# one_dollar_boad.net
KiCad netlist of a schematic drawn in EAGLE
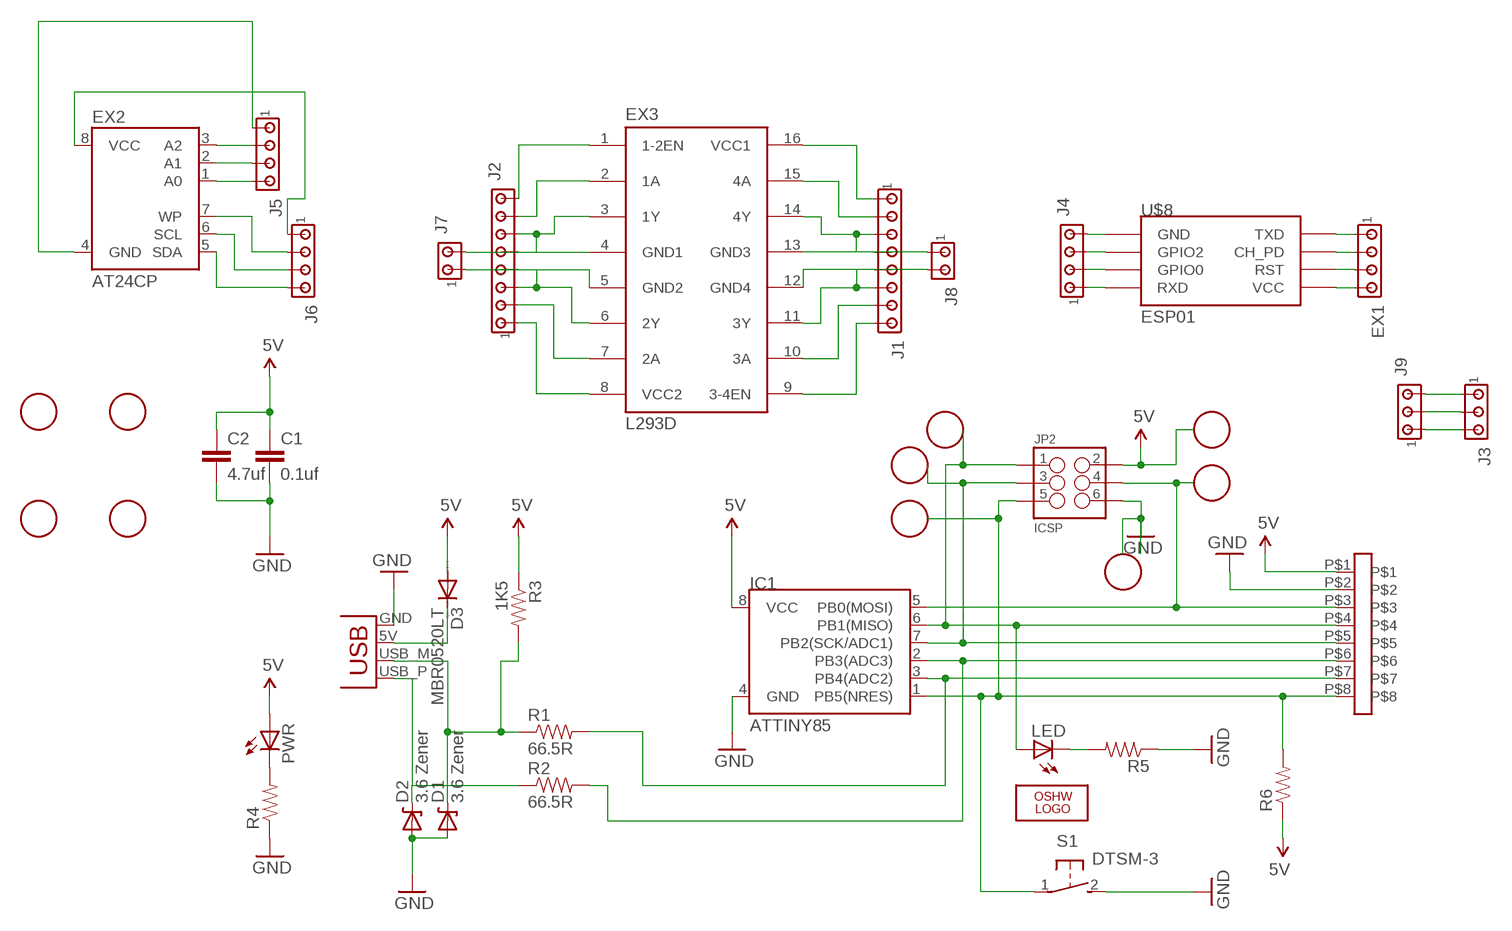
[diagram p0: schematic, sheet 1]

(export (version "E")
  (design (tool "Eeschema 10.0.6"))
  (components
    (comp (ref "C1")
      (value "0.1uf")
      (footprint "eagle-import:0402-CAP")
      (libsource (lib "eagle-import") (part "CAP0402-CAP"))
    )
    (comp (ref "C2")
      (value "4.7uf")
      (footprint "eagle-import:0805")
      (libsource (lib "eagle-import") (part "CAP0805"))
    )
    (comp (ref "CONNECTORBAR1")
      (value "FAMALEBAR01X08")
      (footprint "eagle-import:FEMEABARRA01X08")
      (libsource (lib "eagle-import") (part "FAMALEBAR01X08"))
    )
    (comp (ref "D1")
      (value "3.6 Zener")
      (footprint "eagle-import:SOD-323")
      (libsource (lib "eagle-import") (part "DIODE-ZENER-BZT52"))
    )
    (comp (ref "D2")
      (value "3.6 Zener")
      (footprint "eagle-import:SOD-323")
      (libsource (lib "eagle-import") (part "DIODE-ZENER-BZT52"))
    )
    (comp (ref "D3")
      (value "MBR0520LT")
      (footprint "eagle-import:SOD123")
      (libsource (lib "eagle-import") (part "MBR0520LT"))
    )
    (comp (ref "EX1")
      (value "MTA04-100")
      (footprint "eagle-import:10X04MTA")
      (libsource (lib "eagle-import") (part "MTA04-100"))
    )
    (comp (ref "EX2")
      (value "AT24CP")
      (footprint "eagle-import:DIL08")
      (fields (field (name "MPN") "AT24C1024BW-SH-B"))
      (libsource (lib "eagle-import") (part "AT24CP"))
    )
    (comp (ref "EX3")
      (value "L293D")
      (footprint "eagle-import:DIL16")
      (libsource (lib "eagle-import") (part "L293D"))
    )
    (comp (ref "IC1")
      (value "ATTINY85")
      (footprint "eagle-import:SO08-EIAJ")
      (libsource (lib "eagle-import") (part "ATTINY45"))
    )
    (comp (ref "ICSP1")
      (value "ICSP")
      (footprint "eagle-import:ICSP")
      (libsource (lib "eagle-import") (part "ICSP"))
    )
    (comp (ref "ICSP2")
      (value "ICSP")
      (footprint "eagle-import:ICSP")
      (libsource (lib "eagle-import") (part "ICSP"))
    )
    (comp (ref "ICSP3")
      (value "ICSP")
      (footprint "eagle-import:ICSP")
      (libsource (lib "eagle-import") (part "ICSP"))
    )
    (comp (ref "ICSP4")
      (value "ICSP")
      (footprint "eagle-import:ICSP")
      (libsource (lib "eagle-import") (part "ICSP"))
    )
    (comp (ref "ICSP5")
      (value "ICSP")
      (footprint "eagle-import:ICSP")
      (libsource (lib "eagle-import") (part "ICSP"))
    )
    (comp (ref "ICSP6")
      (value "ICSP")
      (footprint "eagle-import:ICSP")
      (libsource (lib "eagle-import") (part "ICSP"))
    )
    (comp (ref "J1")
      (value "MTA08-100")
      (footprint "eagle-import:10X08MTA")
      (libsource (lib "eagle-import") (part "MTA08-100"))
    )
    (comp (ref "J2")
      (value "MTA08-100")
      (footprint "eagle-import:10X08MTA")
      (libsource (lib "eagle-import") (part "MTA08-100"))
    )
    (comp (ref "J3")
      (value "MTA03-100")
      (footprint "eagle-import:10X03MTA")
      (libsource (lib "eagle-import") (part "MTA03-100"))
    )
    (comp (ref "J4")
      (value "MTA04-100")
      (footprint "eagle-import:10X04MTA")
      (libsource (lib "eagle-import") (part "MTA04-100"))
    )
    (comp (ref "J5")
      (value "MTA04-100")
      (footprint "eagle-import:10X04MTA")
      (libsource (lib "eagle-import") (part "MTA04-100"))
    )
    (comp (ref "J6")
      (value "MTA04-100")
      (footprint "eagle-import:10X04MTA")
      (libsource (lib "eagle-import") (part "MTA04-100"))
    )
    (comp (ref "J7")
      (value "MTA02-100")
      (footprint "eagle-import:10X02MTA")
      (libsource (lib "eagle-import") (part "MTA02-100"))
    )
    (comp (ref "J8")
      (value "MTA02-100")
      (footprint "eagle-import:10X02MTA")
      (libsource (lib "eagle-import") (part "MTA02-100"))
    )
    (comp (ref "J9")
      (value "MTA03-100")
      (footprint "eagle-import:10X03MTA")
      (libsource (lib "eagle-import") (part "MTA03-100"))
    )
    (comp (ref "JP2")
      (value "ICSP")
      (footprint "eagle-import:2X3")
      (libsource (lib "eagle-import") (part "M03X22X3_SILK_MALE_PTH"))
    )
    (comp (ref "LED")
      (value "LED0603")
      (footprint "eagle-import:LED-0603")
      (libsource (lib "eagle-import") (part "LED0603"))
    )
    (comp (ref "LOGO2")
      (value "LOGO-OSHW-10MILX0200-NT")
      (footprint "eagle-import:OSHW_10X200_NOTEXT")
      (libsource (lib "eagle-import") (part "LOGO-OSHW-10MILX0200-NT"))
    )
    (comp (ref "PWR")
      (value "LED0603")
      (footprint "eagle-import:LED-0603")
      (libsource (lib "eagle-import") (part "LED0603"))
    )
    (comp (ref "R1")
      (value "66.5R")
      (footprint "eagle-import:0402-RES")
      (libsource (lib "eagle-import") (part "RESISTOR0402-RES"))
    )
    (comp (ref "R2")
      (value "66.5R")
      (footprint "eagle-import:0402-RES")
      (libsource (lib "eagle-import") (part "RESISTOR0402-RES"))
    )
    (comp (ref "R3")
      (value "1K5")
      (footprint "eagle-import:0402-RES")
      (libsource (lib "eagle-import") (part "RESISTOR0402-RES"))
    )
    (comp (ref "R4")
      (value "RESISTOR0402-RES")
      (footprint "eagle-import:0402-RES")
      (libsource (lib "eagle-import") (part "RESISTOR0402-RES"))
    )
    (comp (ref "R5")
      (value "RESISTOR0402-RES")
      (footprint "eagle-import:0402-RES")
      (libsource (lib "eagle-import") (part "RESISTOR0402-RES"))
    )
    (comp (ref "R6")
      (value "RESISTOR0402-RES")
      (footprint "eagle-import:0402-RES")
      (libsource (lib "eagle-import") (part "SparkFun-Passives_RESISTOR0402-RES"))
    )
    (comp (ref "S1")
      (value "DTSM-3")
      (footprint "eagle-import:DTSM-3")
      (libsource (lib "eagle-import") (part "DTSM-3"))
    )
    (comp (ref "U$8")
      (value "ESP01")
      (footprint "eagle-import:ESP01")
      (libsource (lib "eagle-import") (part "ESP01"))
    )
    (comp (ref "U$9")
      (value "ARDUINOPINAGEM")
      (footprint "eagle-import:ARDUINOPINAGEM")
      (libsource (lib "eagle-import") (part "ARDUINOPINAGEM"))
    )
    (comp (ref "X1")
      (value "USBPCB")
      (footprint "eagle-import:USB-A-PCB")
      (libsource (lib "eagle-import") (part "USBPCB"))
    )
  )
  (nets
    (net (code "1") (name "5V") (class "Default")
      (node (ref "C1") (pin "1") (pinfunction "1_1") (pintype "passive"))
      (node (ref "C2") (pin "1") (pinfunction "1_1") (pintype "passive"))
      (node (ref "CONNECTORBAR1") (pin "P$1") (pinfunction "P$1_P$1") (pintype "bidirectional"))
      (node (ref "D3") (pin "A") (pinfunction "A_A") (pintype "passive"))
      (node (ref "IC1") (pin "8") (pinfunction "VCC_8") (pintype "bidirectional"))
      (node (ref "JP2") (pin "2") (pinfunction "2_2") (pintype "bidirectional"))
      (node (ref "PWR") (pin "A") (pinfunction "A_A") (pintype "passive"))
      (node (ref "R3") (pin "1") (pinfunction "1_1") (pintype "passive"))
      (node (ref "R6") (pin "1") (pinfunction "1_1") (pintype "passive"))
    )
    (net (code "2") (name "GND") (class "Default")
      (node (ref "C1") (pin "2") (pinfunction "2_2") (pintype "passive"))
      (node (ref "C2") (pin "2") (pinfunction "2_2") (pintype "passive"))
      (node (ref "CONNECTORBAR1") (pin "P$2") (pinfunction "P$2_P$2") (pintype "bidirectional"))
      (node (ref "D1") (pin "2") (pinfunction "A_2") (pintype "passive"))
      (node (ref "D2") (pin "2") (pinfunction "A_2") (pintype "passive"))
      (node (ref "IC1") (pin "4") (pinfunction "GND_4") (pintype "bidirectional"))
      (node (ref "JP2") (pin "6") (pinfunction "6_6") (pintype "bidirectional"))
      (node (ref "R4") (pin "1") (pinfunction "1_1") (pintype "passive"))
      (node (ref "R5") (pin "1") (pinfunction "1_1") (pintype "passive"))
      (node (ref "S1") (pin "2") (pinfunction "2_2") (pintype "passive"))
      (node (ref "X1") (pin "GND") (pinfunction "GND_GND") (pintype "bidirectional"))
    )
    (net (code "3") (name "Net-(D1-C)") (class "Default")
      (node (ref "D1") (pin "1") (pinfunction "C_1") (pintype "passive"))
      (node (ref "R1") (pin "1") (pinfunction "1_1") (pintype "passive"))
      (node (ref "R3") (pin "2") (pinfunction "2_2") (pintype "passive"))
      (node (ref "X1") (pin "USB_M") (pinfunction "D-_USB_M") (pintype "bidirectional"))
    )
    (net (code "4") (name "Net-(D2-C)") (class "Default")
      (node (ref "D2") (pin "1") (pinfunction "C_1") (pintype "passive"))
      (node (ref "R2") (pin "1") (pinfunction "1_1") (pintype "passive"))
      (node (ref "X1") (pin "USB_P") (pinfunction "D+_USB_P") (pintype "bidirectional"))
    )
    (net (code "5") (name "Net-(EX1-Pad2)") (class "Default")
      (node (ref "EX1") (pin "2") (pinfunction "2_2") (pintype "passive"))
      (node (ref "U$8") (pin "CH_PD") (pinfunction "CH_PD_CH_PD") (pintype "bidirectional"))
    )
    (net (code "6") (name "Net-(EX1-Pad3)") (class "Default")
      (node (ref "EX1") (pin "3") (pinfunction "3_3") (pintype "passive"))
      (node (ref "U$8") (pin "RST") (pinfunction "RST_RST") (pintype "bidirectional"))
    )
    (net (code "7") (name "Net-(EX1-Pad4)") (class "Default")
      (node (ref "EX1") (pin "4") (pinfunction "4_4") (pintype "passive"))
      (node (ref "U$8") (pin "VCC") (pinfunction "VCC_VCC") (pintype "bidirectional"))
    )
    (net (code "8") (name "Net-(EX2-A0)") (class "Default")
      (node (ref "EX2") (pin "1") (pinfunction "A0_1") (pintype "input"))
      (node (ref "J5") (pin "4") (pinfunction "4_4") (pintype "passive"))
    )
    (net (code "9") (name "Net-(EX2-A1)") (class "Default")
      (node (ref "EX2") (pin "2") (pinfunction "A1_2") (pintype "input"))
      (node (ref "J5") (pin "3") (pinfunction "3_3") (pintype "passive"))
    )
    (net (code "10") (name "Net-(EX2-A2)") (class "Default")
      (node (ref "EX2") (pin "3") (pinfunction "A2_3") (pintype "input"))
      (node (ref "J5") (pin "2") (pinfunction "2_2") (pintype "passive"))
    )
    (net (code "11") (name "Net-(EX2-GND)") (class "Default")
      (node (ref "EX2") (pin "4") (pinfunction "GND_4") (pintype "power_in"))
      (node (ref "J5") (pin "1") (pinfunction "1_1") (pintype "passive"))
    )
    (net (code "12") (name "Net-(EX2-SCL)") (class "Default")
      (node (ref "EX2") (pin "6") (pinfunction "SCL_6") (pintype "bidirectional"))
      (node (ref "J6") (pin "3") (pinfunction "3_3") (pintype "passive"))
    )
    (net (code "13") (name "Net-(EX2-SDA)") (class "Default")
      (node (ref "EX2") (pin "5") (pinfunction "SDA_5") (pintype "bidirectional"))
      (node (ref "J6") (pin "4") (pinfunction "4_4") (pintype "passive"))
    )
    (net (code "14") (name "Net-(EX2-VCC)") (class "Default")
      (node (ref "EX2") (pin "8") (pinfunction "VCC_8") (pintype "power_in"))
      (node (ref "J6") (pin "1") (pinfunction "1_1") (pintype "passive"))
    )
    (net (code "15") (name "Net-(EX2-WP)") (class "Default")
      (node (ref "EX2") (pin "7") (pinfunction "WP_7") (pintype "input"))
      (node (ref "J6") (pin "2") (pinfunction "2_2") (pintype "passive"))
    )
    (net (code "16") (name "Net-(EX3-1-2EN)") (class "Default")
      (node (ref "EX3") (pin "1") (pinfunction "1-2EN_1") (pintype "input"))
      (node (ref "J2") (pin "8") (pinfunction "8_8") (pintype "passive"))
    )
    (net (code "17") (name "Net-(EX3-1A)") (class "Default")
      (node (ref "EX3") (pin "2") (pinfunction "1A_2") (pintype "input"))
      (node (ref "J2") (pin "7") (pinfunction "7_7") (pintype "passive"))
    )
    (net (code "18") (name "Net-(EX3-1Y)") (class "Default")
      (node (ref "EX3") (pin "3") (pinfunction "1Y_3") (pintype "output"))
      (node (ref "J2") (pin "6") (pinfunction "6_6") (pintype "passive"))
      (node (ref "J7") (pin "2") (pinfunction "2_2") (pintype "passive"))
    )
    (net (code "19") (name "Net-(EX3-2A)") (class "Default")
      (node (ref "EX3") (pin "7") (pinfunction "2A_7") (pintype "input"))
      (node (ref "J2") (pin "2") (pinfunction "2_2") (pintype "passive"))
    )
    (net (code "20") (name "Net-(EX3-2Y)") (class "Default")
      (node (ref "EX3") (pin "6") (pinfunction "2Y_6") (pintype "output"))
      (node (ref "J2") (pin "3") (pinfunction "3_3") (pintype "passive"))
      (node (ref "J7") (pin "1") (pinfunction "1_1") (pintype "passive"))
    )
    (net (code "21") (name "Net-(EX3-3-4EN)") (class "Default")
      (node (ref "EX3") (pin "9") (pinfunction "3-4EN_9") (pintype "input"))
      (node (ref "J1") (pin "8") (pinfunction "8_8") (pintype "passive"))
    )
    (net (code "22") (name "Net-(EX3-3A)") (class "Default")
      (node (ref "EX3") (pin "10") (pinfunction "3A_10") (pintype "input"))
      (node (ref "J1") (pin "7") (pinfunction "7_7") (pintype "passive"))
    )
    (net (code "23") (name "Net-(EX3-3Y)") (class "Default")
      (node (ref "EX3") (pin "11") (pinfunction "3Y_11") (pintype "output"))
      (node (ref "J1") (pin "6") (pinfunction "6_6") (pintype "passive"))
      (node (ref "J8") (pin "2") (pinfunction "2_2") (pintype "passive"))
    )
    (net (code "24") (name "Net-(EX3-4A)") (class "Default")
      (node (ref "EX3") (pin "15") (pinfunction "4A_15") (pintype "input"))
      (node (ref "J1") (pin "2") (pinfunction "2_2") (pintype "passive"))
    )
    (net (code "25") (name "Net-(EX3-4Y)") (class "Default")
      (node (ref "EX3") (pin "14") (pinfunction "4Y_14") (pintype "output"))
      (node (ref "J1") (pin "3") (pinfunction "3_3") (pintype "passive"))
      (node (ref "J8") (pin "1") (pinfunction "1_1") (pintype "passive"))
    )
    (net (code "26") (name "Net-(EX3-GND1)") (class "Default")
      (node (ref "EX3") (pin "4") (pinfunction "GND1_4") (pintype "power_in"))
      (node (ref "J2") (pin "5") (pinfunction "5_5") (pintype "passive"))
    )
    (net (code "27") (name "Net-(EX3-GND2)") (class "Default")
      (node (ref "EX3") (pin "5") (pinfunction "GND2_5") (pintype "power_in"))
      (node (ref "J2") (pin "4") (pinfunction "4_4") (pintype "passive"))
    )
    (net (code "28") (name "Net-(EX3-GND3)") (class "Default")
      (node (ref "EX3") (pin "13") (pinfunction "GND3_13") (pintype "power_in"))
      (node (ref "J1") (pin "4") (pinfunction "4_4") (pintype "passive"))
    )
    (net (code "29") (name "Net-(EX3-GND4)") (class "Default")
      (node (ref "EX3") (pin "12") (pinfunction "GND4_12") (pintype "power_in"))
      (node (ref "J1") (pin "5") (pinfunction "5_5") (pintype "passive"))
    )
    (net (code "30") (name "Net-(EX3-VCC1)") (class "Default")
      (node (ref "EX3") (pin "16") (pinfunction "VCC1_16") (pintype "power_in"))
      (node (ref "J1") (pin "1") (pinfunction "1_1") (pintype "passive"))
    )
    (net (code "31") (name "Net-(EX3-VCC2)") (class "Default")
      (node (ref "EX3") (pin "8") (pinfunction "VCC2_8") (pintype "power_in"))
      (node (ref "J2") (pin "1") (pinfunction "1_1") (pintype "passive"))
    )
    (net (code "32") (name "Net-(IC1-PB0(MOSI))") (class "Default")
      (node (ref "CONNECTORBAR1") (pin "P$3") (pinfunction "P$3_P$3") (pintype "bidirectional"))
      (node (ref "IC1") (pin "5") (pinfunction "PB0(MOSI)_5") (pintype "bidirectional"))
      (node (ref "JP2") (pin "4") (pinfunction "4_4") (pintype "bidirectional"))
    )
    (net (code "33") (name "Net-(IC1-PB1(MISO))") (class "Default")
      (node (ref "CONNECTORBAR1") (pin "P$4") (pinfunction "P$4_P$4") (pintype "bidirectional"))
      (node (ref "IC1") (pin "6") (pinfunction "PB1(MISO)_6") (pintype "bidirectional"))
      (node (ref "JP2") (pin "1") (pinfunction "1_1") (pintype "bidirectional"))
      (node (ref "LED") (pin "A") (pinfunction "A_A") (pintype "passive"))
    )
    (net (code "34") (name "Net-(IC1-PB2(SCK{slash}ADC1))") (class "Default")
      (node (ref "CONNECTORBAR1") (pin "P$5") (pinfunction "P$5_P$5") (pintype "bidirectional"))
      (node (ref "IC1") (pin "7") (pinfunction "PB2(SCK/ADC1)_7") (pintype "bidirectional"))
      (node (ref "JP2") (pin "3") (pinfunction "3_3") (pintype "bidirectional"))
    )
    (net (code "35") (name "Net-(IC1-PB3(ADC3))") (class "Default")
      (node (ref "CONNECTORBAR1") (pin "P$6") (pinfunction "P$6_P$6") (pintype "bidirectional"))
      (node (ref "IC1") (pin "2") (pinfunction "PB3(ADC3)_2") (pintype "bidirectional"))
      (node (ref "R2") (pin "2") (pinfunction "2_2") (pintype "passive"))
    )
    (net (code "36") (name "Net-(IC1-PB4(ADC2))") (class "Default")
      (node (ref "CONNECTORBAR1") (pin "P$7") (pinfunction "P$7_P$7") (pintype "bidirectional"))
      (node (ref "IC1") (pin "3") (pinfunction "PB4(ADC2)_3") (pintype "bidirectional"))
      (node (ref "R1") (pin "2") (pinfunction "2_2") (pintype "passive"))
    )
    (net (code "37") (name "Net-(IC1-PB5(NRES))") (class "Default")
      (node (ref "CONNECTORBAR1") (pin "P$8") (pinfunction "P$8_P$8") (pintype "bidirectional"))
      (node (ref "IC1") (pin "1") (pinfunction "PB5(NRES)_1") (pintype "bidirectional"))
      (node (ref "JP2") (pin "5") (pinfunction "5_5") (pintype "bidirectional"))
      (node (ref "R6") (pin "2") (pinfunction "2_2") (pintype "passive"))
      (node (ref "S1") (pin "1") (pinfunction "1_1") (pintype "passive"))
    )
    (net (code "38") (name "Net-(J3-Pad1)") (class "Default")
      (node (ref "J3") (pin "1") (pinfunction "1_1") (pintype "passive"))
      (node (ref "J9") (pin "3") (pinfunction "3_3") (pintype "passive"))
    )
    (net (code "39") (name "Net-(J3-Pad2)") (class "Default")
      (node (ref "J3") (pin "2") (pinfunction "2_2") (pintype "passive"))
      (node (ref "J9") (pin "2") (pinfunction "2_2") (pintype "passive"))
    )
    (net (code "40") (name "Net-(J3-Pad3)") (class "Default")
      (node (ref "J3") (pin "3") (pinfunction "3_3") (pintype "passive"))
      (node (ref "J9") (pin "1") (pinfunction "1_1") (pintype "passive"))
    )
    (net (code "41") (name "Net-(J4-Pad2)") (class "Default")
      (node (ref "J4") (pin "2") (pinfunction "2_2") (pintype "passive"))
      (node (ref "U$8") (pin "GPIO0") (pinfunction "GPIO0_GPIO0") (pintype "bidirectional"))
    )
    (net (code "42") (name "Net-(J4-Pad3)") (class "Default")
      (node (ref "J4") (pin "3") (pinfunction "3_3") (pintype "passive"))
      (node (ref "U$8") (pin "GPIO2") (pinfunction "GPIO2_GPIO2") (pintype "bidirectional"))
    )
    (net (code "43") (name "Net-(J4-Pad4)") (class "Default")
      (node (ref "J4") (pin "4") (pinfunction "4_4") (pintype "passive"))
      (node (ref "U$8") (pin "GND") (pinfunction "GND_GND") (pintype "bidirectional"))
    )
    (net (code "44") (name "Net-(LED-PadC)") (class "Default")
      (node (ref "LED") (pin "C") (pinfunction "C_C") (pintype "passive"))
      (node (ref "R5") (pin "2") (pinfunction "2_2") (pintype "passive"))
    )
    (net (code "45") (name "Net-(PWR-PadC)") (class "Default")
      (node (ref "PWR") (pin "C") (pinfunction "C_C") (pintype "passive"))
      (node (ref "R4") (pin "2") (pinfunction "2_2") (pintype "passive"))
    )
    (net (code "46") (name "Net-(U$8-RXD)") (class "Default")
      (node (ref "J4") (pin "1") (pinfunction "1_1") (pintype "passive"))
      (node (ref "U$8") (pin "RX") (pinfunction "RXD_RX") (pintype "bidirectional"))
    )
    (net (code "47") (name "Net-(U$8-TXD)") (class "Default")
      (node (ref "EX1") (pin "1") (pinfunction "1_1") (pintype "passive"))
      (node (ref "U$8") (pin "TX") (pinfunction "TXD_TX") (pintype "bidirectional"))
    )
    (net (code "48") (name "Net-(X1-VBUS)") (class "Default")
      (node (ref "D3") (pin "C") (pinfunction "C_C") (pintype "passive"))
      (node (ref "X1") (pin "5V") (pinfunction "VBUS_5V") (pintype "bidirectional"))
    )
  )
)
